# uRusset_Meeper_Barc.net
KiCad netlist of a schematic drawn in EAGLE
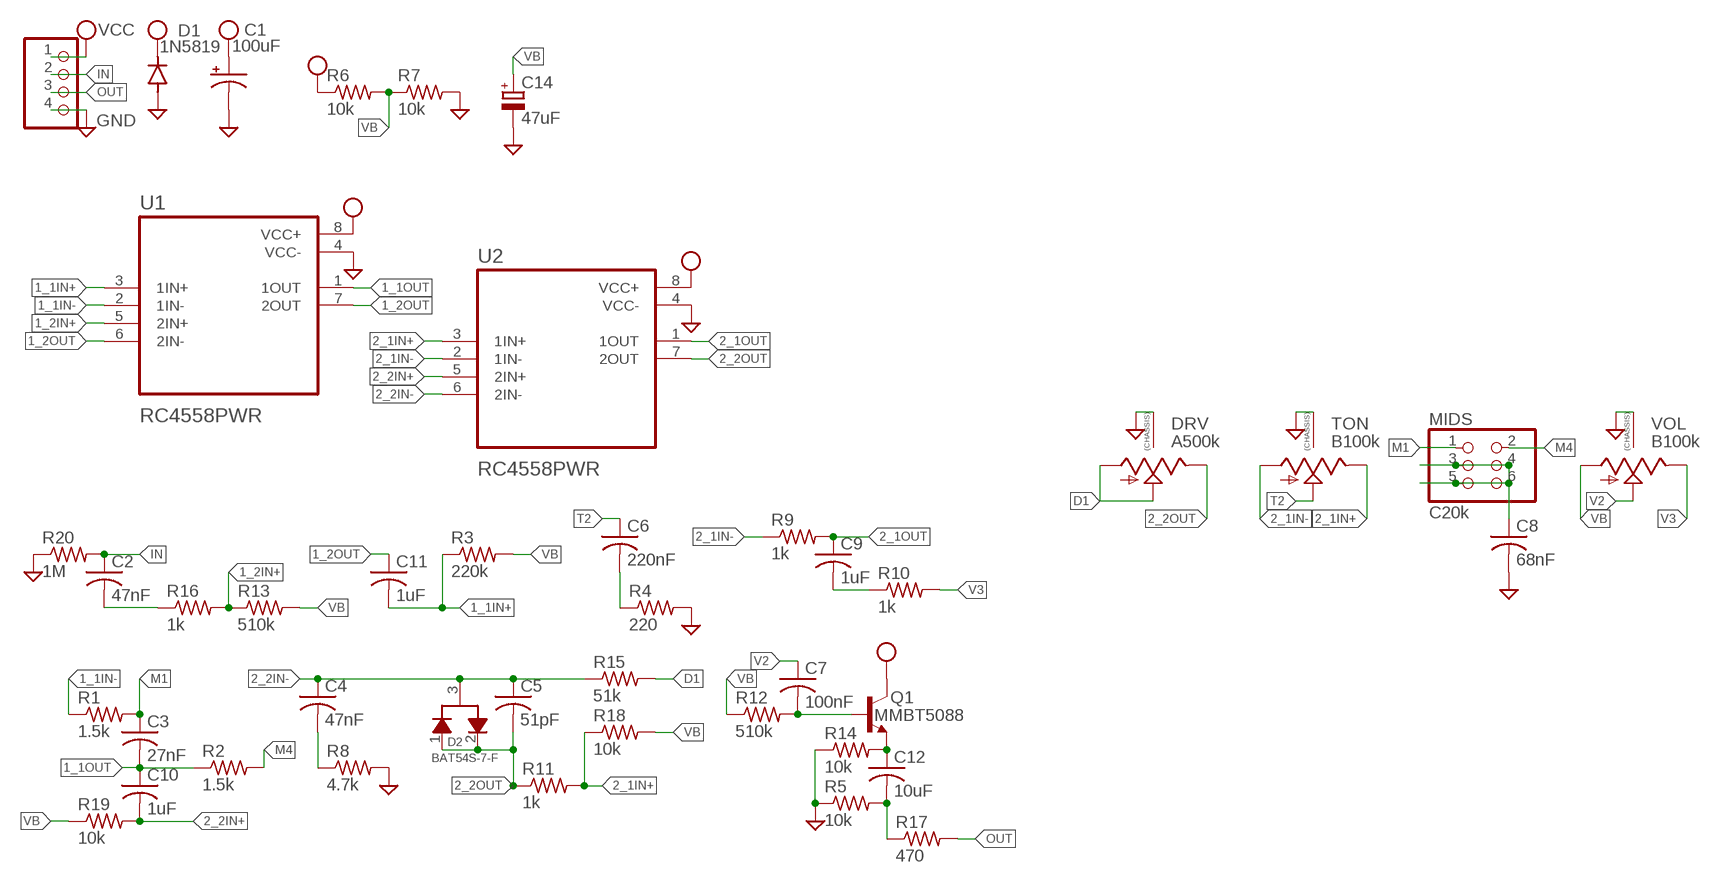
[diagram p0: schematic, sheet 1]

(export (version "E")
  (design (tool "Eeschema 10.0.6"))
  (components
    (comp (ref "C1")
      (value "100uF")
      (footprint "eagle-import:PAN_B_SMD+THRU")
      (libsource (lib "eagle-import") (part "CAP_SMD+THRUPAN_B"))
    )
    (comp (ref "C2")
      (value "47nF")
      (footprint "eagle-import:C0603")
      (libsource (lib "eagle-import") (part "C-USC0603"))
    )
    (comp (ref "C3")
      (value "27nF")
      (footprint "eagle-import:C0603")
      (libsource (lib "eagle-import") (part "C-USC0603"))
    )
    (comp (ref "C4")
      (value "47nF")
      (footprint "eagle-import:C0603")
      (libsource (lib "eagle-import") (part "C-USC0603"))
    )
    (comp (ref "C5")
      (value "51pF")
      (footprint "eagle-import:C0603")
      (libsource (lib "eagle-import") (part "C-USC0603"))
    )
    (comp (ref "C6")
      (value "220nF")
      (footprint "eagle-import:C0603")
      (libsource (lib "eagle-import") (part "C-USC0603"))
    )
    (comp (ref "C7")
      (value "100nF")
      (footprint "eagle-import:C0603")
      (libsource (lib "eagle-import") (part "C-USC0603"))
    )
    (comp (ref "C8")
      (value "68nF")
      (footprint "eagle-import:C0603")
      (libsource (lib "eagle-import") (part "C-USC0603"))
    )
    (comp (ref "C9")
      (value "1uF")
      (footprint "eagle-import:C0805")
      (libsource (lib "eagle-import") (part "C-USC0805"))
    )
    (comp (ref "C10")
      (value "1uF")
      (footprint "eagle-import:C0805")
      (libsource (lib "eagle-import") (part "C-USC0805"))
    )
    (comp (ref "C11")
      (value "1uF")
      (footprint "eagle-import:C0805")
      (libsource (lib "eagle-import") (part "C-USC0805"))
    )
    (comp (ref "C12")
      (value "10uF")
      (footprint "eagle-import:C1206")
      (libsource (lib "eagle-import") (part "C-USC1206"))
    )
    (comp (ref "C14")
      (value "47uF")
      (footprint "eagle-import:CAPMP3216X180N")
      (libsource (lib "eagle-import") (part "C-POLTANTALUM-1206(3216-METRIC)_"))
    )
    (comp (ref "D1")
      (value "1N5819")
      (footprint "eagle-import:SOD123")
      (libsource (lib "eagle-import") (part "DIODE-SOD123"))
    )
    (comp (ref "D2")
      (value "BAT54S-7-F")
      (footprint "eagle-import:SOT23-3")
      (fields
        (field (name "DIGIKEY_PART_NUMBER") "BAT54S-FDITR-ND")
        (field (name "MANUFACTURER") "Diodes Incorporated")
        (field (name "CREATED_BY") "PCBLayout.com")
      )
      (libsource (lib "eagle-import") (part "BAT54S-7-F"))
    )
    (comp (ref "DRV")
      (value "A500k")
      (footprint "eagle-import:9MM_SNAP-IN_POT")
      (libsource (lib "eagle-import") (part "9MM_SNAP-IN_POT_CHASSIS"))
    )
    (comp (ref "JP1")
      (value "PINHD-1X4")
      (footprint "eagle-import:1X04")
      (libsource (lib "eagle-import") (part "PINHD-1X4"))
    )
    (comp (ref "MIDS")
      (value "C20k")
      (footprint "eagle-import:2X03")
      (libsource (lib "eagle-import") (part "PINHD-2X3"))
    )
    (comp (ref "Q1")
      (value "MMBT5088")
      (footprint "eagle-import:SOT23-BEC")
      (fields (field (name "MF") "ON Semiconductor"))
      (libsource (lib "eagle-import") (part "MMBT5088"))
    )
    (comp (ref "R1")
      (value "1.5k")
      (footprint "eagle-import:R0603")
      (libsource (lib "eagle-import") (part "R-US_R0603"))
    )
    (comp (ref "R2")
      (value "1.5k")
      (footprint "eagle-import:R0603")
      (libsource (lib "eagle-import") (part "R-US_R0603"))
    )
    (comp (ref "R3")
      (value "220k")
      (footprint "eagle-import:R0603")
      (libsource (lib "eagle-import") (part "R-US_R0603"))
    )
    (comp (ref "R4")
      (value "220")
      (footprint "eagle-import:R0603")
      (libsource (lib "eagle-import") (part "R-US_R0603"))
    )
    (comp (ref "R5")
      (value "10k")
      (footprint "eagle-import:R0603")
      (libsource (lib "eagle-import") (part "R-US_R0603"))
    )
    (comp (ref "R6")
      (value "10k")
      (footprint "eagle-import:R0603")
      (libsource (lib "eagle-import") (part "R-US_R0603"))
    )
    (comp (ref "R7")
      (value "10k")
      (footprint "eagle-import:R0603")
      (libsource (lib "eagle-import") (part "R-US_R0603"))
    )
    (comp (ref "R8")
      (value "4.7k")
      (footprint "eagle-import:R0603")
      (libsource (lib "eagle-import") (part "R-US_R0603"))
    )
    (comp (ref "R9")
      (value "1k")
      (footprint "eagle-import:R0603")
      (libsource (lib "eagle-import") (part "R-US_R0603"))
    )
    (comp (ref "R10")
      (value "1k")
      (footprint "eagle-import:R0603")
      (libsource (lib "eagle-import") (part "R-US_R0603"))
    )
    (comp (ref "R11")
      (value "1k")
      (footprint "eagle-import:R0603")
      (libsource (lib "eagle-import") (part "R-US_R0603"))
    )
    (comp (ref "R12")
      (value "510k")
      (footprint "eagle-import:R0603")
      (libsource (lib "eagle-import") (part "R-US_R0603"))
    )
    (comp (ref "R13")
      (value "510k")
      (footprint "eagle-import:R0603")
      (libsource (lib "eagle-import") (part "R-US_R0603"))
    )
    (comp (ref "R14")
      (value "10k")
      (footprint "eagle-import:R0603")
      (libsource (lib "eagle-import") (part "R-US_R0603"))
    )
    (comp (ref "R15")
      (value "51k")
      (footprint "eagle-import:R0603")
      (libsource (lib "eagle-import") (part "R-US_R0603"))
    )
    (comp (ref "R16")
      (value "1k")
      (footprint "eagle-import:R0603")
      (libsource (lib "eagle-import") (part "R-US_R0603"))
    )
    (comp (ref "R17")
      (value "470")
      (footprint "eagle-import:R0603")
      (libsource (lib "eagle-import") (part "R-US_R0603"))
    )
    (comp (ref "R18")
      (value "10k")
      (footprint "eagle-import:R0603")
      (libsource (lib "eagle-import") (part "R-US_R0603"))
    )
    (comp (ref "R19")
      (value "10k")
      (footprint "eagle-import:R0603")
      (libsource (lib "eagle-import") (part "R-US_R0603"))
    )
    (comp (ref "R20")
      (value "1M")
      (footprint "eagle-import:R0603")
      (libsource (lib "eagle-import") (part "R-US_R0603"))
    )
    (comp (ref "TON")
      (value "B100k")
      (footprint "eagle-import:9MM_SNAP-IN_POT")
      (libsource (lib "eagle-import") (part "9MM_SNAP-IN_POT_CHASSIS"))
    )
    (comp (ref "U1")
      (value "RC4558PWR")
      (footprint "eagle-import:SOP65P640X120-8N")
      (fields (field (name "MF") "Texas Instruments"))
      (libsource (lib "eagle-import") (part "RC4558PWR"))
    )
    (comp (ref "U2")
      (value "RC4558PWR")
      (footprint "eagle-import:SOP65P640X120-8N")
      (fields (field (name "MF") "Texas Instruments"))
      (libsource (lib "eagle-import") (part "RC4558PWR"))
    )
    (comp (ref "VOL")
      (value "B100k")
      (footprint "eagle-import:9MM_SNAP-IN_POT")
      (libsource (lib "eagle-import") (part "9MM_SNAP-IN_POT_CHASSIS"))
    )
  )
  (nets
    (net (code "1") (name "1_1IN+") (class "Default")
      (node (ref "C11") (pin "2") (pinfunction "2_2") (pintype "passive"))
      (node (ref "R3") (pin "1") (pinfunction "1_1") (pintype "passive"))
      (node (ref "U1") (pin "3") (pinfunction "1IN+_3") (pintype "input"))
    )
    (net (code "2") (name "1_1IN-") (class "Default")
      (node (ref "R1") (pin "1") (pinfunction "1_1") (pintype "passive"))
      (node (ref "U1") (pin "2") (pinfunction "1IN-_2") (pintype "input"))
    )
    (net (code "3") (name "1_1OUT") (class "Default")
      (node (ref "C10") (pin "1") (pinfunction "1_1") (pintype "passive"))
      (node (ref "C3") (pin "2") (pinfunction "2_2") (pintype "passive"))
      (node (ref "R2") (pin "1") (pinfunction "1_1") (pintype "passive"))
      (node (ref "U1") (pin "1") (pinfunction "1OUT_1") (pintype "output"))
    )
    (net (code "4") (name "1_2IN+") (class "Default")
      (node (ref "R13") (pin "1") (pinfunction "1_1") (pintype "passive"))
      (node (ref "R16") (pin "2") (pinfunction "2_2") (pintype "passive"))
      (node (ref "U1") (pin "5") (pinfunction "2IN+_5") (pintype "input"))
    )
    (net (code "5") (name "1_2OUT") (class "Default")
      (node (ref "C11") (pin "1") (pinfunction "1_1") (pintype "passive"))
      (node (ref "U1") (pin "6") (pinfunction "2IN-_6") (pintype "input"))
      (node (ref "U1") (pin "7") (pinfunction "2OUT_7") (pintype "output"))
    )
    (net (code "6") (name "2_1IN+") (class "Default")
      (node (ref "R11") (pin "2") (pinfunction "2_2") (pintype "passive"))
      (node (ref "R18") (pin "1") (pinfunction "1_1") (pintype "passive"))
      (node (ref "TON") (pin "3") (pinfunction "E_3") (pintype "passive"))
      (node (ref "U2") (pin "3") (pinfunction "1IN+_3") (pintype "input"))
    )
    (net (code "7") (name "2_1IN-") (class "Default")
      (node (ref "R9") (pin "1") (pinfunction "1_1") (pintype "passive"))
      (node (ref "TON") (pin "1") (pinfunction "A_1") (pintype "passive"))
      (node (ref "U2") (pin "2") (pinfunction "1IN-_2") (pintype "input"))
    )
    (net (code "8") (name "2_1OUT") (class "Default")
      (node (ref "C9") (pin "1") (pinfunction "1_1") (pintype "passive"))
      (node (ref "R9") (pin "2") (pinfunction "2_2") (pintype "passive"))
      (node (ref "U2") (pin "1") (pinfunction "1OUT_1") (pintype "output"))
    )
    (net (code "9") (name "2_2IN+") (class "Default")
      (node (ref "C10") (pin "2") (pinfunction "2_2") (pintype "passive"))
      (node (ref "R19") (pin "2") (pinfunction "2_2") (pintype "passive"))
      (node (ref "U2") (pin "5") (pinfunction "2IN+_5") (pintype "input"))
    )
    (net (code "10") (name "2_2IN-") (class "Default")
      (node (ref "C4") (pin "1") (pinfunction "1_1") (pintype "passive"))
      (node (ref "C5") (pin "1") (pinfunction "1_1") (pintype "passive"))
      (node (ref "D2") (pin "3") (pinfunction "3_3") (pintype "passive"))
      (node (ref "R15") (pin "1") (pinfunction "1_1") (pintype "passive"))
      (node (ref "U2") (pin "6") (pinfunction "2IN-_6") (pintype "input"))
    )
    (net (code "11") (name "2_2OUT") (class "Default")
      (node (ref "C5") (pin "2") (pinfunction "2_2") (pintype "passive"))
      (node (ref "D2") (pin "1") (pinfunction "1_1") (pintype "passive"))
      (node (ref "D2") (pin "2") (pinfunction "2_2") (pintype "passive"))
      (node (ref "DRV") (pin "3") (pinfunction "E_3") (pintype "passive"))
      (node (ref "R11") (pin "1") (pinfunction "1_1") (pintype "passive"))
      (node (ref "U2") (pin "7") (pinfunction "2OUT_7") (pintype "output"))
    )
    (net (code "12") (name "D1") (class "Default")
      (node (ref "DRV") (pin "1") (pinfunction "A_1") (pintype "passive"))
      (node (ref "DRV") (pin "2") (pinfunction "S_2") (pintype "passive"))
      (node (ref "R15") (pin "2") (pinfunction "2_2") (pintype "passive"))
    )
    (net (code "13") (name "GND") (class "Default")
      (node (ref "C1") (pin "-") (pinfunction "-_-") (pintype "passive"))
      (node (ref "C1") (pin "--") (pinfunction "-_--") (pintype "passive"))
      (node (ref "C14") (pin "2") (pinfunction "-_2") (pintype "passive"))
      (node (ref "C8") (pin "2") (pinfunction "2_2") (pintype "passive"))
      (node (ref "D1") (pin "A") (pinfunction "A_A") (pintype "passive"))
      (node (ref "DRV") (pin "CHASSIS1") (pinfunction "P$1_CHASSIS1") (pintype "passive"))
      (node (ref "DRV") (pin "CHASSIS2") (pinfunction "P$1_CHASSIS2") (pintype "passive"))
      (node (ref "JP1") (pin "4") (pinfunction "4_4") (pintype "passive"))
      (node (ref "R14") (pin "1") (pinfunction "1_1") (pintype "passive"))
      (node (ref "R20") (pin "1") (pinfunction "1_1") (pintype "passive"))
      (node (ref "R4") (pin "2") (pinfunction "2_2") (pintype "passive"))
      (node (ref "R5") (pin "1") (pinfunction "1_1") (pintype "passive"))
      (node (ref "R7") (pin "2") (pinfunction "2_2") (pintype "passive"))
      (node (ref "R8") (pin "2") (pinfunction "2_2") (pintype "passive"))
      (node (ref "TON") (pin "CHASSIS1") (pinfunction "P$1_CHASSIS1") (pintype "passive"))
      (node (ref "TON") (pin "CHASSIS2") (pinfunction "P$1_CHASSIS2") (pintype "passive"))
      (node (ref "U1") (pin "4") (pinfunction "VCC-_4") (pintype "power_in"))
      (node (ref "U2") (pin "4") (pinfunction "VCC-_4") (pintype "power_in"))
      (node (ref "VOL") (pin "CHASSIS1") (pinfunction "P$1_CHASSIS1") (pintype "passive"))
      (node (ref "VOL") (pin "CHASSIS2") (pinfunction "P$1_CHASSIS2") (pintype "passive"))
    )
    (net (code "14") (name "IN") (class "Default")
      (node (ref "C2") (pin "1") (pinfunction "1_1") (pintype "passive"))
      (node (ref "JP1") (pin "2") (pinfunction "2_2") (pintype "passive"))
      (node (ref "R20") (pin "2") (pinfunction "2_2") (pintype "passive"))
    )
    (net (code "15") (name "M1") (class "Default")
      (node (ref "C3") (pin "1") (pinfunction "1_1") (pintype "passive"))
      (node (ref "MIDS") (pin "1") (pinfunction "1_1") (pintype "passive"))
      (node (ref "R1") (pin "2") (pinfunction "2_2") (pintype "passive"))
    )
    (net (code "16") (name "M4") (class "Default")
      (node (ref "MIDS") (pin "2") (pinfunction "2_2") (pintype "passive"))
      (node (ref "R2") (pin "2") (pinfunction "2_2") (pintype "passive"))
    )
    (net (code "17") (name "Net-(C2-Pad2)") (class "Default")
      (node (ref "C2") (pin "2") (pinfunction "2_2") (pintype "passive"))
      (node (ref "R16") (pin "1") (pinfunction "1_1") (pintype "passive"))
    )
    (net (code "18") (name "Net-(C4-Pad2)") (class "Default")
      (node (ref "C4") (pin "2") (pinfunction "2_2") (pintype "passive"))
      (node (ref "R8") (pin "1") (pinfunction "1_1") (pintype "passive"))
    )
    (net (code "19") (name "Net-(C6-Pad2)") (class "Default")
      (node (ref "C6") (pin "2") (pinfunction "2_2") (pintype "passive"))
      (node (ref "R4") (pin "1") (pinfunction "1_1") (pintype "passive"))
    )
    (net (code "20") (name "Net-(C7-Pad2)") (class "Default")
      (node (ref "C7") (pin "2") (pinfunction "2_2") (pintype "passive"))
      (node (ref "Q1") (pin "B") (pinfunction "B_B") (pintype "passive"))
      (node (ref "R12") (pin "2") (pinfunction "2_2") (pintype "passive"))
    )
    (net (code "21") (name "Net-(C8-Pad1)") (class "Default")
      (node (ref "C8") (pin "1") (pinfunction "1_1") (pintype "passive"))
      (node (ref "MIDS") (pin "3") (pinfunction "3_3") (pintype "passive"))
      (node (ref "MIDS") (pin "4") (pinfunction "4_4") (pintype "passive"))
      (node (ref "MIDS") (pin "5") (pinfunction "5_5") (pintype "passive"))
      (node (ref "MIDS") (pin "6") (pinfunction "6_6") (pintype "passive"))
    )
    (net (code "22") (name "Net-(C9-Pad2)") (class "Default")
      (node (ref "C9") (pin "2") (pinfunction "2_2") (pintype "passive"))
      (node (ref "R10") (pin "1") (pinfunction "1_1") (pintype "passive"))
    )
    (net (code "23") (name "Net-(C12-Pad1)") (class "Default")
      (node (ref "C12") (pin "1") (pinfunction "1_1") (pintype "passive"))
      (node (ref "Q1") (pin "E") (pinfunction "E_E") (pintype "passive"))
      (node (ref "R14") (pin "2") (pinfunction "2_2") (pintype "passive"))
    )
    (net (code "24") (name "Net-(C12-Pad2)") (class "Default")
      (node (ref "C12") (pin "2") (pinfunction "2_2") (pintype "passive"))
      (node (ref "R17") (pin "1") (pinfunction "1_1") (pintype "passive"))
      (node (ref "R5") (pin "2") (pinfunction "2_2") (pintype "passive"))
    )
    (net (code "25") (name "OUT") (class "Default")
      (node (ref "JP1") (pin "3") (pinfunction "3_3") (pintype "passive"))
      (node (ref "R17") (pin "2") (pinfunction "2_2") (pintype "passive"))
    )
    (net (code "26") (name "T2") (class "Default")
      (node (ref "C6") (pin "1") (pinfunction "1_1") (pintype "passive"))
      (node (ref "TON") (pin "2") (pinfunction "S_2") (pintype "passive"))
    )
    (net (code "27") (name "V2") (class "Default")
      (node (ref "C7") (pin "1") (pinfunction "1_1") (pintype "passive"))
      (node (ref "VOL") (pin "2") (pinfunction "S_2") (pintype "passive"))
    )
    (net (code "28") (name "V3") (class "Default")
      (node (ref "R10") (pin "2") (pinfunction "2_2") (pintype "passive"))
      (node (ref "VOL") (pin "3") (pinfunction "E_3") (pintype "passive"))
    )
    (net (code "29") (name "VB") (class "Default")
      (node (ref "C14") (pin "1") (pinfunction "+_1") (pintype "passive"))
      (node (ref "R12") (pin "1") (pinfunction "1_1") (pintype "passive"))
      (node (ref "R13") (pin "2") (pinfunction "2_2") (pintype "passive"))
      (node (ref "R18") (pin "2") (pinfunction "2_2") (pintype "passive"))
      (node (ref "R19") (pin "1") (pinfunction "1_1") (pintype "passive"))
      (node (ref "R3") (pin "2") (pinfunction "2_2") (pintype "passive"))
      (node (ref "R6") (pin "2") (pinfunction "2_2") (pintype "passive"))
      (node (ref "R7") (pin "1") (pinfunction "1_1") (pintype "passive"))
      (node (ref "VOL") (pin "1") (pinfunction "A_1") (pintype "passive"))
    )
    (net (code "30") (name "VCC") (class "Default")
      (node (ref "C1") (pin "+") (pinfunction "+_+") (pintype "passive"))
      (node (ref "C1") (pin "++") (pinfunction "+_++") (pintype "passive"))
      (node (ref "D1") (pin "C") (pinfunction "C_C") (pintype "passive"))
      (node (ref "JP1") (pin "1") (pinfunction "1_1") (pintype "passive"))
      (node (ref "Q1") (pin "C") (pinfunction "C_C") (pintype "passive"))
      (node (ref "R6") (pin "1") (pinfunction "1_1") (pintype "passive"))
      (node (ref "U1") (pin "8") (pinfunction "VCC+_8") (pintype "power_in"))
      (node (ref "U2") (pin "8") (pinfunction "VCC+_8") (pintype "power_in"))
    )
  )
)
